# Sheet1.net
KiCad netlist of a schematic drawn in Altium Designer
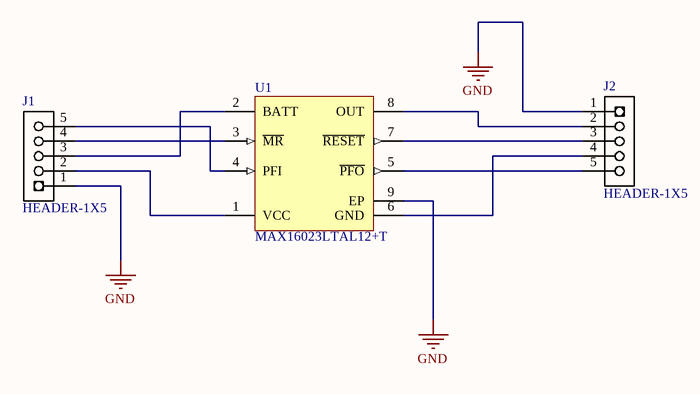
[diagram p0: Sheet1.SchDoc]

(export (version "E")
  (design (tool "Eeschema 10.0.6"))
  (components
    (comp (ref "J1")
      (value "HEADER-1X5")
      (footprint "HEADER-1X5")
      (description "PINHEADER 1X5")
      (libsource (lib "vh_altium_library") (part "HEADER-1X5"))
    )
    (comp (ref "J2")
      (value "HEADER-1X5")
      (footprint "HEADER-1X5")
      (description "PINHEADER 1X5")
      (libsource (lib "vh_altium_library") (part "HEADER-1X5"))
    )
    (comp (ref "U1")
      (value "MAX16023LTAL12+T")
      (footprint "T823+1_V")
      (libsource (lib "Maxim Supervisors, Voltage Monitors and Sequencers") (part "MAX16023LTAL12+T"))
    )
  )
  (nets
    (net (code "1") (name "GND") (class "Default")
      (node (ref "J1") (pin "1") (pintype "passive"))
      (node (ref "J2") (pin "1") (pintype "passive"))
      (node (ref "U1") (pin "9") (pinfunction "EP_9") (pintype "power_in"))
    )
    (net (code "2") (name "Net-(U1-BATT)") (class "Default")
      (node (ref "J1") (pin "3") (pintype "passive"))
      (node (ref "U1") (pin "2") (pinfunction "BATT_2") (pintype "power_in"))
    )
    (net (code "3") (name "Net-(U1-GND)") (class "Default")
      (node (ref "J2") (pin "4") (pintype "passive"))
      (node (ref "U1") (pin "6") (pinfunction "GND_6") (pintype "power_in"))
    )
    (net (code "4") (name "Net-(U1-OUT)") (class "Default")
      (node (ref "J2") (pin "2") (pintype "passive"))
      (node (ref "U1") (pin "8") (pinfunction "OUT_8") (pintype "power_in"))
    )
    (net (code "5") (name "Net-(U1-PFI)") (class "Default")
      (node (ref "J1") (pin "5") (pintype "passive"))
      (node (ref "U1") (pin "4") (pinfunction "PFI_4") (pintype "input"))
    )
    (net (code "6") (name "Net-(U1-VCC)") (class "Default")
      (node (ref "J1") (pin "2") (pintype "passive"))
      (node (ref "U1") (pin "1") (pinfunction "VCC_1") (pintype "power_in"))
    )
    (net (code "7") (name "Net-(U1-~{MR})") (class "Default")
      (node (ref "J1") (pin "4") (pintype "passive"))
      (node (ref "U1") (pin "3") (pinfunction "~{MR}_3") (pintype "input"))
    )
    (net (code "8") (name "Net-(U1-~{PFO})") (class "Default")
      (node (ref "J2") (pin "5") (pintype "passive"))
      (node (ref "U1") (pin "5") (pinfunction "~{PFO}_5") (pintype "output"))
    )
    (net (code "9") (name "Net-(U1-~{RESET})") (class "Default")
      (node (ref "J2") (pin "3") (pintype "passive"))
      (node (ref "U1") (pin "7") (pinfunction "~{RESET}_7") (pintype "output"))
    )
  )
)
